# can.net
KiCad netlist of a schematic drawn in Altium Designer
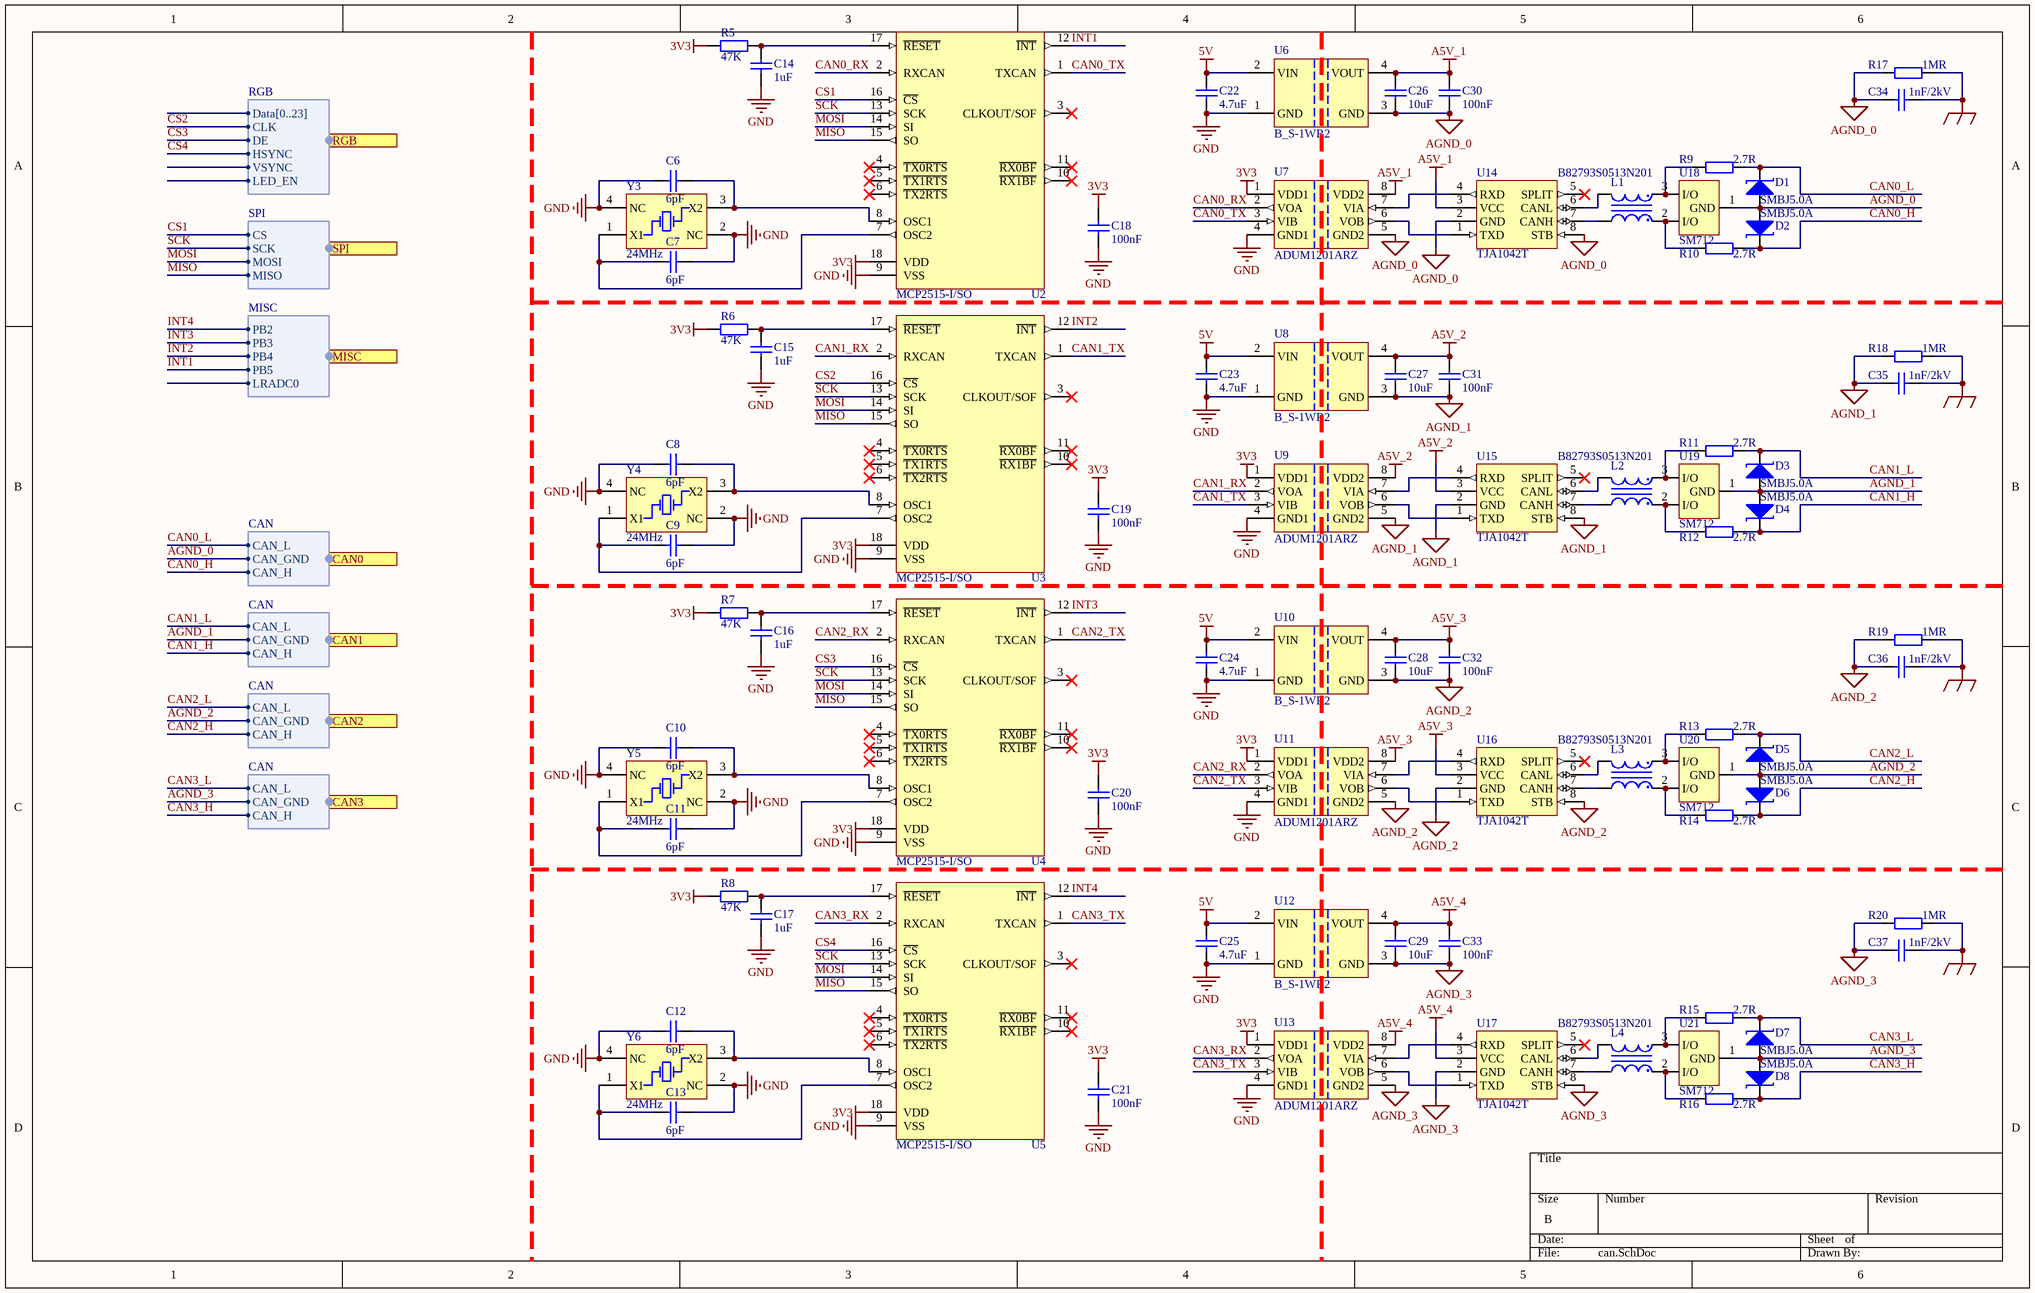
[diagram p0: can.SchDoc]

(export (version "E")
  (design (tool "Eeschema 10.0.6"))
  (components
    (comp (ref "C6")
      (value "6pF")
      (footprint "CAPC1608L")
      (description "Capacitor")
      (fields (field (name "PUBLISHER") "Altium Limited"))
      (libsource (lib "Peace的集成库") (part "Cap1"))
    )
    (comp (ref "C7")
      (value "6pF")
      (footprint "CAPC1608L")
      (description "Capacitor")
      (fields (field (name "PUBLISHER") "Altium Limited"))
      (libsource (lib "Peace的集成库") (part "Cap1"))
    )
    (comp (ref "C8")
      (value "6pF")
      (footprint "CAPC1608L")
      (description "Capacitor")
      (fields (field (name "PUBLISHER") "Altium Limited"))
      (libsource (lib "Peace的集成库") (part "Cap1"))
    )
    (comp (ref "C9")
      (value "6pF")
      (footprint "CAPC1608L")
      (description "Capacitor")
      (fields (field (name "PUBLISHER") "Altium Limited"))
      (libsource (lib "Peace的集成库") (part "Cap1"))
    )
    (comp (ref "C10")
      (value "6pF")
      (footprint "CAPC1608L")
      (description "Capacitor")
      (fields (field (name "PUBLISHER") "Altium Limited"))
      (libsource (lib "Peace的集成库") (part "Cap1"))
    )
    (comp (ref "C11")
      (value "6pF")
      (footprint "CAPC1608L")
      (description "Capacitor")
      (fields (field (name "PUBLISHER") "Altium Limited"))
      (libsource (lib "Peace的集成库") (part "Cap1"))
    )
    (comp (ref "C12")
      (value "6pF")
      (footprint "CAPC1608L")
      (description "Capacitor")
      (fields (field (name "PUBLISHER") "Altium Limited"))
      (libsource (lib "Peace的集成库") (part "Cap1"))
    )
    (comp (ref "C13")
      (value "6pF")
      (footprint "CAPC1608L")
      (description "Capacitor")
      (fields (field (name "PUBLISHER") "Altium Limited"))
      (libsource (lib "Peace的集成库") (part "Cap1"))
    )
    (comp (ref "C14")
      (value "1uF")
      (footprint "CAPC1608L")
      (description "Capacitor")
      (fields (field (name "PUBLISHER") "Altium Limited"))
      (libsource (lib "Peace的集成库") (part "Cap1"))
    )
    (comp (ref "C15")
      (value "1uF")
      (footprint "CAPC1608L")
      (description "Capacitor")
      (fields (field (name "PUBLISHER") "Altium Limited"))
      (libsource (lib "Peace的集成库") (part "Cap1"))
    )
    (comp (ref "C16")
      (value "1uF")
      (footprint "CAPC1608L")
      (description "Capacitor")
      (fields (field (name "PUBLISHER") "Altium Limited"))
      (libsource (lib "Peace的集成库") (part "Cap1"))
    )
    (comp (ref "C17")
      (value "1uF")
      (footprint "CAPC1608L")
      (description "Capacitor")
      (fields (field (name "PUBLISHER") "Altium Limited"))
      (libsource (lib "Peace的集成库") (part "Cap1"))
    )
    (comp (ref "C18")
      (value "100nF")
      (footprint "CAPC1608L")
      (description "Capacitor")
      (fields (field (name "PUBLISHER") "Altium Limited"))
      (libsource (lib "Peace的集成库") (part "Cap1"))
    )
    (comp (ref "C19")
      (value "100nF")
      (footprint "CAPC1608L")
      (description "Capacitor")
      (fields (field (name "PUBLISHER") "Altium Limited"))
      (libsource (lib "Peace的集成库") (part "Cap1"))
    )
    (comp (ref "C20")
      (value "100nF")
      (footprint "CAPC1608L")
      (description "Capacitor")
      (fields (field (name "PUBLISHER") "Altium Limited"))
      (libsource (lib "Peace的集成库") (part "Cap1"))
    )
    (comp (ref "C21")
      (value "100nF")
      (footprint "CAPC1608L")
      (description "Capacitor")
      (fields (field (name "PUBLISHER") "Altium Limited"))
      (libsource (lib "Peace的集成库") (part "Cap1"))
    )
    (comp (ref "C22")
      (value "4.7uF")
      (footprint "CAPC2012L")
      (description "Capacitor")
      (fields (field (name "PUBLISHER") "Altium Limited"))
      (libsource (lib "Peace的集成库") (part "Cap1"))
    )
    (comp (ref "C23")
      (value "4.7uF")
      (footprint "CAPC2012L")
      (description "Capacitor")
      (fields (field (name "PUBLISHER") "Altium Limited"))
      (libsource (lib "Peace的集成库") (part "Cap1"))
    )
    (comp (ref "C24")
      (value "4.7uF")
      (footprint "CAPC2012L")
      (description "Capacitor")
      (fields (field (name "PUBLISHER") "Altium Limited"))
      (libsource (lib "Peace的集成库") (part "Cap1"))
    )
    (comp (ref "C25")
      (value "4.7uF")
      (footprint "CAPC2012L")
      (description "Capacitor")
      (fields (field (name "PUBLISHER") "Altium Limited"))
      (libsource (lib "Peace的集成库") (part "Cap1"))
    )
    (comp (ref "C26")
      (value "10uF")
      (footprint "CAPC2012L")
      (description "Capacitor")
      (fields (field (name "PUBLISHER") "Altium Limited"))
      (libsource (lib "Peace的集成库") (part "Cap1"))
    )
    (comp (ref "C27")
      (value "10uF")
      (footprint "CAPC2012L")
      (description "Capacitor")
      (fields (field (name "PUBLISHER") "Altium Limited"))
      (libsource (lib "Peace的集成库") (part "Cap1"))
    )
    (comp (ref "C28")
      (value "10uF")
      (footprint "CAPC2012L")
      (description "Capacitor")
      (fields (field (name "PUBLISHER") "Altium Limited"))
      (libsource (lib "Peace的集成库") (part "Cap1"))
    )
    (comp (ref "C29")
      (value "10uF")
      (footprint "CAPC2012L")
      (description "Capacitor")
      (fields (field (name "PUBLISHER") "Altium Limited"))
      (libsource (lib "Peace的集成库") (part "Cap1"))
    )
    (comp (ref "C30")
      (value "100nF")
      (footprint "CAPC1608L")
      (description "Capacitor")
      (fields (field (name "PUBLISHER") "Altium Limited"))
      (libsource (lib "Peace的集成库") (part "Cap1"))
    )
    (comp (ref "C31")
      (value "100nF")
      (footprint "CAPC1608L")
      (description "Capacitor")
      (fields (field (name "PUBLISHER") "Altium Limited"))
      (libsource (lib "Peace的集成库") (part "Cap1"))
    )
    (comp (ref "C32")
      (value "100nF")
      (footprint "CAPC1608L")
      (description "Capacitor")
      (fields (field (name "PUBLISHER") "Altium Limited"))
      (libsource (lib "Peace的集成库") (part "Cap1"))
    )
    (comp (ref "C33")
      (value "100nF")
      (footprint "CAPC1608L")
      (description "Capacitor")
      (fields (field (name "PUBLISHER") "Altium Limited"))
      (libsource (lib "Peace的集成库") (part "Cap1"))
    )
    (comp (ref "C34")
      (value "1nF/2kV")
      (footprint "CAPC3216L")
      (description "Capacitor")
      (fields (field (name "PUBLISHER") "Altium Limited"))
      (libsource (lib "Peace的集成库") (part "Cap1"))
    )
    (comp (ref "C35")
      (value "1nF/2kV")
      (footprint "CAPC3216L")
      (description "Capacitor")
      (fields (field (name "PUBLISHER") "Altium Limited"))
      (libsource (lib "Peace的集成库") (part "Cap1"))
    )
    (comp (ref "C36")
      (value "1nF/2kV")
      (footprint "CAPC3216L")
      (description "Capacitor")
      (fields (field (name "PUBLISHER") "Altium Limited"))
      (libsource (lib "Peace的集成库") (part "Cap1"))
    )
    (comp (ref "C37")
      (value "1nF/2kV")
      (footprint "CAPC3216L")
      (description "Capacitor")
      (fields (field (name "PUBLISHER") "Altium Limited"))
      (libsource (lib "Peace的集成库") (part "Cap1"))
    )
    (comp (ref "D1")
      (value "SMBJ5.0A")
      (footprint "DO-214AA")
      (description "Transient Voltage Suppression (TVS) Diode")
      (fields (field (name "PUBLISHER") "Altium Limited"))
      (libsource (lib "Peace的集成库") (part "Tranzorb1"))
    )
    (comp (ref "D2")
      (value "SMBJ5.0A")
      (footprint "DO-214AA")
      (description "Transient Voltage Suppression (TVS) Diode")
      (fields (field (name "PUBLISHER") "Altium Limited"))
      (libsource (lib "Peace的集成库") (part "Tranzorb1"))
    )
    (comp (ref "D3")
      (value "SMBJ5.0A")
      (footprint "DO-214AA")
      (description "Transient Voltage Suppression (TVS) Diode")
      (fields (field (name "PUBLISHER") "Altium Limited"))
      (libsource (lib "Peace的集成库") (part "Tranzorb1"))
    )
    (comp (ref "D4")
      (value "SMBJ5.0A")
      (footprint "DO-214AA")
      (description "Transient Voltage Suppression (TVS) Diode")
      (fields (field (name "PUBLISHER") "Altium Limited"))
      (libsource (lib "Peace的集成库") (part "Tranzorb1"))
    )
    (comp (ref "D5")
      (value "SMBJ5.0A")
      (footprint "DO-214AA")
      (description "Transient Voltage Suppression (TVS) Diode")
      (fields (field (name "PUBLISHER") "Altium Limited"))
      (libsource (lib "Peace的集成库") (part "Tranzorb1"))
    )
    (comp (ref "D6")
      (value "SMBJ5.0A")
      (footprint "DO-214AA")
      (description "Transient Voltage Suppression (TVS) Diode")
      (fields (field (name "PUBLISHER") "Altium Limited"))
      (libsource (lib "Peace的集成库") (part "Tranzorb1"))
    )
    (comp (ref "D7")
      (value "SMBJ5.0A")
      (footprint "DO-214AA")
      (description "Transient Voltage Suppression (TVS) Diode")
      (fields (field (name "PUBLISHER") "Altium Limited"))
      (libsource (lib "Peace的集成库") (part "Tranzorb1"))
    )
    (comp (ref "D8")
      (value "SMBJ5.0A")
      (footprint "DO-214AA")
      (description "Transient Voltage Suppression (TVS) Diode")
      (fields (field (name "PUBLISHER") "Altium Limited"))
      (libsource (lib "Peace的集成库") (part "Tranzorb1"))
    )
    (comp (ref "L1")
      (value "B82793S0513N201")
      (footprint "IND0163-B")
      (description "共模电感")
      (fields (field (name "PUBLISHER") "Altium Limited"))
      (libsource (lib "Peace的集成库") (part "Inductor1"))
    )
    (comp (ref "L2")
      (value "B82793S0513N201")
      (footprint "IND0163-B")
      (description "共模电感")
      (fields (field (name "PUBLISHER") "Altium Limited"))
      (libsource (lib "Peace的集成库") (part "Inductor1"))
    )
    (comp (ref "L3")
      (value "B82793S0513N201")
      (footprint "IND0163-B")
      (description "共模电感")
      (fields (field (name "PUBLISHER") "Altium Limited"))
      (libsource (lib "Peace的集成库") (part "Inductor1"))
    )
    (comp (ref "L4")
      (value "B82793S0513N201")
      (footprint "IND0163-B")
      (description "共模电感")
      (fields (field (name "PUBLISHER") "Altium Limited"))
      (libsource (lib "Peace的集成库") (part "Inductor1"))
    )
    (comp (ref "R5")
      (value "47K")
      (footprint "RESC1608L")
      (description "Resistor")
      (fields (field (name "PUBLISHER") "Altium Limited"))
      (libsource (lib "") (part "Res1_1"))
    )
    (comp (ref "R6")
      (value "47K")
      (footprint "RESC1608L")
      (description "Resistor")
      (fields (field (name "PUBLISHER") "Altium Limited"))
      (libsource (lib "") (part "Res1_1"))
    )
    (comp (ref "R7")
      (value "47K")
      (footprint "RESC1608L")
      (description "Resistor")
      (fields (field (name "PUBLISHER") "Altium Limited"))
      (libsource (lib "") (part "Res1_1"))
    )
    (comp (ref "R8")
      (value "47K")
      (footprint "RESC1608L")
      (description "Resistor")
      (fields (field (name "PUBLISHER") "Altium Limited"))
      (libsource (lib "") (part "Res1_1"))
    )
    (comp (ref "R9")
      (value "2.7R")
      (footprint "RESC3216L")
      (description "Resistor")
      (fields (field (name "PUBLISHER") "Altium Limited"))
      (libsource (lib "Peace的集成库") (part "Res1"))
    )
    (comp (ref "R10")
      (value "2.7R")
      (footprint "RESC3216L")
      (description "Resistor")
      (fields (field (name "PUBLISHER") "Altium Limited"))
      (libsource (lib "Peace的集成库") (part "Res1"))
    )
    (comp (ref "R11")
      (value "2.7R")
      (footprint "RESC3216L")
      (description "Resistor")
      (fields (field (name "PUBLISHER") "Altium Limited"))
      (libsource (lib "Peace的集成库") (part "Res1"))
    )
    (comp (ref "R12")
      (value "2.7R")
      (footprint "RESC3216L")
      (description "Resistor")
      (fields (field (name "PUBLISHER") "Altium Limited"))
      (libsource (lib "Peace的集成库") (part "Res1"))
    )
    (comp (ref "R13")
      (value "2.7R")
      (footprint "RESC3216L")
      (description "Resistor")
      (fields (field (name "PUBLISHER") "Altium Limited"))
      (libsource (lib "Peace的集成库") (part "Res1"))
    )
    (comp (ref "R14")
      (value "2.7R")
      (footprint "RESC3216L")
      (description "Resistor")
      (fields (field (name "PUBLISHER") "Altium Limited"))
      (libsource (lib "Peace的集成库") (part "Res1"))
    )
    (comp (ref "R15")
      (value "2.7R")
      (footprint "RESC3216L")
      (description "Resistor")
      (fields (field (name "PUBLISHER") "Altium Limited"))
      (libsource (lib "Peace的集成库") (part "Res1"))
    )
    (comp (ref "R16")
      (value "2.7R")
      (footprint "RESC3216L")
      (description "Resistor")
      (fields (field (name "PUBLISHER") "Altium Limited"))
      (libsource (lib "Peace的集成库") (part "Res1"))
    )
    (comp (ref "R17")
      (value "1MR")
      (footprint "RESC3216L")
      (description "Resistor")
      (fields (field (name "PUBLISHER") "Altium Limited"))
      (libsource (lib "Peace的集成库") (part "Res1"))
    )
    (comp (ref "R18")
      (value "1MR")
      (footprint "RESC3216L")
      (description "Resistor")
      (fields (field (name "PUBLISHER") "Altium Limited"))
      (libsource (lib "Peace的集成库") (part "Res1"))
    )
    (comp (ref "R19")
      (value "1MR")
      (footprint "RESC3216L")
      (description "Resistor")
      (fields (field (name "PUBLISHER") "Altium Limited"))
      (libsource (lib "Peace的集成库") (part "Res1"))
    )
    (comp (ref "R20")
      (value "1MR")
      (footprint "RESC3216L")
      (description "Resistor")
      (fields (field (name "PUBLISHER") "Altium Limited"))
      (libsource (lib "Peace的集成库") (part "Res1"))
    )
    (comp (ref "U2")
      (value "MCP2515-I/SO")
      (footprint "SOIC18_N")
      (description "Stand-Alone CAN Controller With SPI Interface, 18-Pin SOIC, Industrial Temperature")
      (fields (field (name "PUBLISHER") "Altium Limited"))
      (libsource (lib "Peace的集成库") (part "MCP2515-I/SO"))
    )
    (comp (ref "U3")
      (value "MCP2515-I/SO")
      (footprint "SOIC18_N")
      (description "Stand-Alone CAN Controller With SPI Interface, 18-Pin SOIC, Industrial Temperature")
      (fields (field (name "PUBLISHER") "Altium Limited"))
      (libsource (lib "Peace的集成库") (part "MCP2515-I/SO"))
    )
    (comp (ref "U4")
      (value "MCP2515-I/SO")
      (footprint "SOIC18_N")
      (description "Stand-Alone CAN Controller With SPI Interface, 18-Pin SOIC, Industrial Temperature")
      (fields (field (name "PUBLISHER") "Altium Limited"))
      (libsource (lib "Peace的集成库") (part "MCP2515-I/SO"))
    )
    (comp (ref "U5")
      (value "MCP2515-I/SO")
      (footprint "SOIC18_N")
      (description "Stand-Alone CAN Controller With SPI Interface, 18-Pin SOIC, Industrial Temperature")
      (fields (field (name "PUBLISHER") "Altium Limited"))
      (libsource (lib "Peace的集成库") (part "MCP2515-I/SO"))
    )
    (comp (ref "U6")
      (value "B_S-1WR2")
      (footprint "B_S-1WR2")
      (description "DC/DC 模块电源 1W，定电压输入，隔离非稳压单路输出")
      (libsource (lib "原理图库") (part "B_S-1WR2"))
    )
    (comp (ref "U7")
      (value "ADUM1201ARZ")
      (footprint "SOIC8_L")
      (description "双通道数字隔离器（1/1通道方向性）")
      (libsource (lib "Peace的集成库") (part "ADUM1201"))
    )
    (comp (ref "U8")
      (value "B_S-1WR2")
      (footprint "B_S-1WR2")
      (description "DC/DC 模块电源 1W，定电压输入，隔离非稳压单路输出")
      (libsource (lib "原理图库") (part "B_S-1WR2"))
    )
    (comp (ref "U9")
      (value "ADUM1201ARZ")
      (footprint "SOIC8_L")
      (description "双通道数字隔离器（1/1通道方向性）")
      (libsource (lib "Peace的集成库") (part "ADUM1201"))
    )
    (comp (ref "U10")
      (value "B_S-1WR2")
      (footprint "B_S-1WR2")
      (description "DC/DC 模块电源 1W，定电压输入，隔离非稳压单路输出")
      (libsource (lib "原理图库") (part "B_S-1WR2"))
    )
    (comp (ref "U11")
      (value "ADUM1201ARZ")
      (footprint "SOIC8_L")
      (description "双通道数字隔离器（1/1通道方向性）")
      (libsource (lib "Peace的集成库") (part "ADUM1201"))
    )
    (comp (ref "U12")
      (value "B_S-1WR2")
      (footprint "B_S-1WR2")
      (description "DC/DC 模块电源 1W，定电压输入，隔离非稳压单路输出")
      (libsource (lib "原理图库") (part "B_S-1WR2"))
    )
    (comp (ref "U13")
      (value "ADUM1201ARZ")
      (footprint "SOIC8_L")
      (description "双通道数字隔离器（1/1通道方向性）")
      (libsource (lib "Peace的集成库") (part "ADUM1201"))
    )
    (comp (ref "U14")
      (value "TJA1042T")
      (footprint "SOIC8_L")
      (description "具有待机模式的高速CAN收发器")
      (libsource (lib "Peace的集成库") (part "TJA1042T"))
    )
    (comp (ref "U15")
      (value "TJA1042T")
      (footprint "SOIC8_L")
      (description "具有待机模式的高速CAN收发器")
      (libsource (lib "Peace的集成库") (part "TJA1042T"))
    )
    (comp (ref "U16")
      (value "TJA1042T")
      (footprint "SOIC8_L")
      (description "具有待机模式的高速CAN收发器")
      (libsource (lib "Peace的集成库") (part "TJA1042T"))
    )
    (comp (ref "U17")
      (value "TJA1042T")
      (footprint "SOIC8_L")
      (description "具有待机模式的高速CAN收发器")
      (libsource (lib "Peace的集成库") (part "TJA1042T"))
    )
    (comp (ref "U18") (value "SM712") (footprint "SOT23_L") (libsource (lib "Peace的集成库") (part "Tranzorb2")))
    (comp (ref "U19") (value "SM712") (footprint "SOT23_L") (libsource (lib "Peace的集成库") (part "Tranzorb2")))
    (comp (ref "U20") (value "SM712") (footprint "SOT23_L") (libsource (lib "Peace的集成库") (part "Tranzorb2")))
    (comp (ref "U21") (value "SM712") (footprint "SOT23_L") (libsource (lib "Peace的集成库") (part "Tranzorb2")))
    (comp (ref "Y3")
      (value "24MHz")
      (footprint "XTAL-3225")
      (description "Crystal Oscillator")
      (fields (field (name "PUBLISHER") "Altium Limited"))
      (libsource (lib "Peace的集成库") (part "XTAL_PASSIVE_4"))
    )
    (comp (ref "Y4")
      (value "24MHz")
      (footprint "XTAL-3225")
      (description "Crystal Oscillator")
      (fields (field (name "PUBLISHER") "Altium Limited"))
      (libsource (lib "Peace的集成库") (part "XTAL_PASSIVE_4"))
    )
    (comp (ref "Y5")
      (value "24MHz")
      (footprint "XTAL-3225")
      (description "Crystal Oscillator")
      (fields (field (name "PUBLISHER") "Altium Limited"))
      (libsource (lib "Peace的集成库") (part "XTAL_PASSIVE_4"))
    )
    (comp (ref "Y6")
      (value "24MHz")
      (footprint "XTAL-3225")
      (description "Crystal Oscillator")
      (fields (field (name "PUBLISHER") "Altium Limited"))
      (libsource (lib "Peace的集成库") (part "XTAL_PASSIVE_4"))
    )
  )
  (nets
    (net (code "6") (name "/CAN0_H") (class "Default")
      (node (ref "D2") (pin "2") (pinfunction "K_2") (pintype "passive"))
      (node (ref "R10") (pin "1") (pinfunction "1_1") (pintype "passive"))
    )
    (net (code "7") (name "/CAN0_L") (class "Default")
      (node (ref "D1") (pin "2") (pinfunction "K_2") (pintype "passive"))
      (node (ref "R9") (pin "1") (pinfunction "1_1") (pintype "passive"))
    )
    (net (code "8") (name "/CAN0_RX") (class "Default")
      (node (ref "U2") (pin "2") (pinfunction "RXCAN_2") (pintype "input"))
      (node (ref "U7") (pin "2") (pinfunction "VOA_2") (pintype "output"))
    )
    (net (code "9") (name "/CAN0_TX") (class "Default")
      (node (ref "U2") (pin "1") (pinfunction "TXCAN_1") (pintype "output"))
      (node (ref "U7") (pin "3") (pinfunction "VIB_3") (pintype "input"))
    )
    (net (code "10") (name "/CAN1_H") (class "Default")
      (node (ref "D4") (pin "2") (pinfunction "K_2") (pintype "passive"))
      (node (ref "R12") (pin "1") (pinfunction "1_1") (pintype "passive"))
    )
    (net (code "11") (name "/CAN1_L") (class "Default")
      (node (ref "D3") (pin "2") (pinfunction "K_2") (pintype "passive"))
      (node (ref "R11") (pin "1") (pinfunction "1_1") (pintype "passive"))
    )
    (net (code "12") (name "/CAN1_RX") (class "Default")
      (node (ref "U3") (pin "2") (pinfunction "RXCAN_2") (pintype "input"))
      (node (ref "U9") (pin "2") (pinfunction "VOA_2") (pintype "output"))
    )
    (net (code "13") (name "/CAN1_TX") (class "Default")
      (node (ref "U3") (pin "1") (pinfunction "TXCAN_1") (pintype "output"))
      (node (ref "U9") (pin "3") (pinfunction "VIB_3") (pintype "input"))
    )
    (net (code "14") (name "/CAN2_H") (class "Default")
      (node (ref "D6") (pin "2") (pinfunction "K_2") (pintype "passive"))
      (node (ref "R14") (pin "1") (pinfunction "1_1") (pintype "passive"))
    )
    (net (code "15") (name "/CAN2_L") (class "Default")
      (node (ref "D5") (pin "2") (pinfunction "K_2") (pintype "passive"))
      (node (ref "R13") (pin "1") (pinfunction "1_1") (pintype "passive"))
    )
    (net (code "16") (name "/CAN2_RX") (class "Default")
      (node (ref "U11") (pin "2") (pinfunction "VOA_2") (pintype "output"))
      (node (ref "U4") (pin "2") (pinfunction "RXCAN_2") (pintype "input"))
    )
    (net (code "17") (name "/CAN2_TX") (class "Default")
      (node (ref "U11") (pin "3") (pinfunction "VIB_3") (pintype "input"))
      (node (ref "U4") (pin "1") (pinfunction "TXCAN_1") (pintype "output"))
    )
    (net (code "18") (name "/CAN3_H") (class "Default")
      (node (ref "D8") (pin "2") (pinfunction "K_2") (pintype "passive"))
      (node (ref "R16") (pin "1") (pinfunction "1_1") (pintype "passive"))
    )
    (net (code "19") (name "/CAN3_L") (class "Default")
      (node (ref "D7") (pin "2") (pinfunction "K_2") (pintype "passive"))
      (node (ref "R15") (pin "1") (pinfunction "1_1") (pintype "passive"))
    )
    (net (code "20") (name "/CAN3_RX") (class "Default")
      (node (ref "U13") (pin "2") (pinfunction "VOA_2") (pintype "output"))
      (node (ref "U5") (pin "2") (pinfunction "RXCAN_2") (pintype "input"))
    )
    (net (code "21") (name "/CAN3_TX") (class "Default")
      (node (ref "U13") (pin "3") (pinfunction "VIB_3") (pintype "input"))
      (node (ref "U5") (pin "1") (pinfunction "TXCAN_1") (pintype "output"))
    )
    (net (code "22") (name "/CS1") (class "Default")
      (node (ref "U2") (pin "16") (pinfunction "~{CS}_16") (pintype "input"))
    )
    (net (code "23") (name "/CS2") (class "Default")
      (node (ref "U3") (pin "16") (pinfunction "~{CS}_16") (pintype "input"))
    )
    (net (code "24") (name "/CS3") (class "Default")
      (node (ref "U4") (pin "16") (pinfunction "~{CS}_16") (pintype "input"))
    )
    (net (code "25") (name "/CS4") (class "Default")
      (node (ref "U5") (pin "16") (pinfunction "~{CS}_16") (pintype "input"))
    )
    (net (code "26") (name "/INT1") (class "Default")
      (node (ref "U2") (pin "12") (pinfunction "~{INT}_12") (pintype "output"))
    )
    (net (code "27") (name "/INT2") (class "Default")
      (node (ref "U3") (pin "12") (pinfunction "~{INT}_12") (pintype "output"))
    )
    (net (code "28") (name "/INT3") (class "Default")
      (node (ref "U4") (pin "12") (pinfunction "~{INT}_12") (pintype "output"))
    )
    (net (code "29") (name "/INT4") (class "Default")
      (node (ref "U5") (pin "12") (pinfunction "~{INT}_12") (pintype "output"))
    )
    (net (code "30") (name "/MISO") (class "Default")
      (node (ref "U2") (pin "15") (pinfunction "SO_15") (pintype "output"))
      (node (ref "U3") (pin "15") (pinfunction "SO_15") (pintype "output"))
      (node (ref "U4") (pin "15") (pinfunction "SO_15") (pintype "output"))
      (node (ref "U5") (pin "15") (pinfunction "SO_15") (pintype "output"))
    )
    (net (code "31") (name "/MOSI") (class "Default")
      (node (ref "U2") (pin "14") (pinfunction "SI_14") (pintype "input"))
      (node (ref "U3") (pin "14") (pinfunction "SI_14") (pintype "input"))
      (node (ref "U4") (pin "14") (pinfunction "SI_14") (pintype "input"))
      (node (ref "U5") (pin "14") (pinfunction "SI_14") (pintype "input"))
    )
    (net (code "33") (name "/SCK") (class "Default")
      (node (ref "U2") (pin "13") (pinfunction "SCK_13") (pintype "input"))
      (node (ref "U3") (pin "13") (pinfunction "SCK_13") (pintype "input"))
      (node (ref "U4") (pin "13") (pinfunction "SCK_13") (pintype "input"))
      (node (ref "U5") (pin "13") (pinfunction "SCK_13") (pintype "input"))
    )
    (net (code "38") (name "3V3") (class "Default")
      (node (ref "C18") (pin "2") (pinfunction "2_2") (pintype "passive"))
      (node (ref "C19") (pin "2") (pinfunction "2_2") (pintype "passive"))
      (node (ref "C20") (pin "2") (pinfunction "2_2") (pintype "passive"))
      (node (ref "C21") (pin "2") (pinfunction "2_2") (pintype "passive"))
      (node (ref "R5") (pin "1") (pinfunction "1_1") (pintype "passive"))
      (node (ref "R6") (pin "1") (pinfunction "1_1") (pintype "passive"))
      (node (ref "R7") (pin "1") (pinfunction "1_1") (pintype "passive"))
      (node (ref "R8") (pin "1") (pinfunction "1_1") (pintype "passive"))
      (node (ref "U11") (pin "1") (pinfunction "VDD1_1") (pintype "power_in"))
      (node (ref "U13") (pin "1") (pinfunction "VDD1_1") (pintype "power_in"))
      (node (ref "U2") (pin "18") (pinfunction "VDD_18") (pintype "power_in"))
      (node (ref "U3") (pin "18") (pinfunction "VDD_18") (pintype "power_in"))
      (node (ref "U4") (pin "18") (pinfunction "VDD_18") (pintype "power_in"))
      (node (ref "U5") (pin "18") (pinfunction "VDD_18") (pintype "power_in"))
      (node (ref "U7") (pin "1") (pinfunction "VDD1_1") (pintype "power_in"))
      (node (ref "U9") (pin "1") (pinfunction "VDD1_1") (pintype "power_in"))
    )
    (net (code "39") (name "5V") (class "Default")
      (node (ref "C22") (pin "2") (pinfunction "2_2") (pintype "passive"))
      (node (ref "C23") (pin "2") (pinfunction "2_2") (pintype "passive"))
      (node (ref "C24") (pin "2") (pinfunction "2_2") (pintype "passive"))
      (node (ref "C25") (pin "2") (pinfunction "2_2") (pintype "passive"))
      (node (ref "U10") (pin "2") (pinfunction "VIN_2") (pintype "power_in"))
      (node (ref "U12") (pin "2") (pinfunction "VIN_2") (pintype "power_in"))
      (node (ref "U6") (pin "2") (pinfunction "VIN_2") (pintype "power_in"))
      (node (ref "U8") (pin "2") (pinfunction "VIN_2") (pintype "power_in"))
    )
    (net (code "40") (name "A5V_1") (class "Default")
      (node (ref "C26") (pin "2") (pinfunction "2_2") (pintype "passive"))
      (node (ref "C30") (pin "1") (pinfunction "1_1") (pintype "passive"))
      (node (ref "U14") (pin "3") (pinfunction "VCC_3") (pintype "power_in"))
      (node (ref "U6") (pin "4") (pinfunction "VOUT_4") (pintype "power_in"))
      (node (ref "U7") (pin "8") (pinfunction "VDD2_8") (pintype "power_in"))
    )
    (net (code "41") (name "A5V_2") (class "Default")
      (node (ref "C27") (pin "2") (pinfunction "2_2") (pintype "passive"))
      (node (ref "C31") (pin "1") (pinfunction "1_1") (pintype "passive"))
      (node (ref "U15") (pin "3") (pinfunction "VCC_3") (pintype "power_in"))
      (node (ref "U8") (pin "4") (pinfunction "VOUT_4") (pintype "power_in"))
      (node (ref "U9") (pin "8") (pinfunction "VDD2_8") (pintype "power_in"))
    )
    (net (code "42") (name "A5V_3") (class "Default")
      (node (ref "C28") (pin "2") (pinfunction "2_2") (pintype "passive"))
      (node (ref "C32") (pin "1") (pinfunction "1_1") (pintype "passive"))
      (node (ref "U10") (pin "4") (pinfunction "VOUT_4") (pintype "power_in"))
      (node (ref "U11") (pin "8") (pinfunction "VDD2_8") (pintype "power_in"))
      (node (ref "U16") (pin "3") (pinfunction "VCC_3") (pintype "power_in"))
    )
    (net (code "43") (name "A5V_4") (class "Default")
      (node (ref "C29") (pin "2") (pinfunction "2_2") (pintype "passive"))
      (node (ref "C33") (pin "1") (pinfunction "1_1") (pintype "passive"))
      (node (ref "U12") (pin "4") (pinfunction "VOUT_4") (pintype "power_in"))
      (node (ref "U13") (pin "8") (pinfunction "VDD2_8") (pintype "power_in"))
      (node (ref "U17") (pin "3") (pinfunction "VCC_3") (pintype "power_in"))
    )
    (net (code "44") (name "AGND_0") (class "Default")
      (node (ref "C26") (pin "1") (pinfunction "1_1") (pintype "passive"))
      (node (ref "C30") (pin "2") (pinfunction "2_2") (pintype "passive"))
      (node (ref "C34") (pin "1") (pinfunction "1_1") (pintype "passive"))
      (node (ref "D1") (pin "1") (pinfunction "A_1") (pintype "passive"))
      (node (ref "D2") (pin "1") (pinfunction "A_1") (pintype "passive"))
      (node (ref "R17") (pin "2") (pinfunction "2_2") (pintype "passive"))
      (node (ref "U14") (pin "2") (pinfunction "GND_2") (pintype "power_in"))
      (node (ref "U14") (pin "8") (pinfunction "STB_8") (pintype "input"))
      (node (ref "U18") (pin "1") (pinfunction "GND_1") (pintype "power_in"))
      (node (ref "U6") (pin "3") (pinfunction "GND_3") (pintype "power_in"))
      (node (ref "U7") (pin "5") (pinfunction "GND2_5") (pintype "power_in"))
    )
    (net (code "45") (name "AGND_1") (class "Default")
      (node (ref "C27") (pin "1") (pinfunction "1_1") (pintype "passive"))
      (node (ref "C31") (pin "2") (pinfunction "2_2") (pintype "passive"))
      (node (ref "C35") (pin "1") (pinfunction "1_1") (pintype "passive"))
      (node (ref "D3") (pin "1") (pinfunction "A_1") (pintype "passive"))
      (node (ref "D4") (pin "1") (pinfunction "A_1") (pintype "passive"))
      (node (ref "R18") (pin "2") (pinfunction "2_2") (pintype "passive"))
      (node (ref "U15") (pin "2") (pinfunction "GND_2") (pintype "power_in"))
      (node (ref "U15") (pin "8") (pinfunction "STB_8") (pintype "input"))
      (node (ref "U19") (pin "1") (pinfunction "GND_1") (pintype "power_in"))
      (node (ref "U8") (pin "3") (pinfunction "GND_3") (pintype "power_in"))
      (node (ref "U9") (pin "5") (pinfunction "GND2_5") (pintype "power_in"))
    )
    (net (code "46") (name "AGND_2") (class "Default")
      (node (ref "C28") (pin "1") (pinfunction "1_1") (pintype "passive"))
      (node (ref "C32") (pin "2") (pinfunction "2_2") (pintype "passive"))
      (node (ref "C36") (pin "1") (pinfunction "1_1") (pintype "passive"))
      (node (ref "D5") (pin "1") (pinfunction "A_1") (pintype "passive"))
      (node (ref "D6") (pin "1") (pinfunction "A_1") (pintype "passive"))
      (node (ref "R19") (pin "2") (pinfunction "2_2") (pintype "passive"))
      (node (ref "U10") (pin "3") (pinfunction "GND_3") (pintype "power_in"))
      (node (ref "U11") (pin "5") (pinfunction "GND2_5") (pintype "power_in"))
      (node (ref "U16") (pin "2") (pinfunction "GND_2") (pintype "power_in"))
      (node (ref "U16") (pin "8") (pinfunction "STB_8") (pintype "input"))
      (node (ref "U20") (pin "1") (pinfunction "GND_1") (pintype "power_in"))
    )
    (net (code "47") (name "AGND_3") (class "Default")
      (node (ref "C29") (pin "1") (pinfunction "1_1") (pintype "passive"))
      (node (ref "C33") (pin "2") (pinfunction "2_2") (pintype "passive"))
      (node (ref "C37") (pin "1") (pinfunction "1_1") (pintype "passive"))
      (node (ref "D7") (pin "1") (pinfunction "A_1") (pintype "passive"))
      (node (ref "D8") (pin "1") (pinfunction "A_1") (pintype "passive"))
      (node (ref "R20") (pin "2") (pinfunction "2_2") (pintype "passive"))
      (node (ref "U12") (pin "3") (pinfunction "GND_3") (pintype "power_in"))
      (node (ref "U13") (pin "5") (pinfunction "GND2_5") (pintype "power_in"))
      (node (ref "U17") (pin "2") (pinfunction "GND_2") (pintype "power_in"))
      (node (ref "U17") (pin "8") (pinfunction "STB_8") (pintype "input"))
      (node (ref "U21") (pin "1") (pinfunction "GND_1") (pintype "power_in"))
    )
    (net (code "48") (name "EARTH") (class "Default")
      (node (ref "C34") (pin "2") (pinfunction "2_2") (pintype "passive"))
      (node (ref "C35") (pin "2") (pinfunction "2_2") (pintype "passive"))
      (node (ref "C36") (pin "2") (pinfunction "2_2") (pintype "passive"))
      (node (ref "C37") (pin "2") (pinfunction "2_2") (pintype "passive"))
      (node (ref "R17") (pin "1") (pinfunction "1_1") (pintype "passive"))
      (node (ref "R18") (pin "1") (pinfunction "1_1") (pintype "passive"))
      (node (ref "R19") (pin "1") (pinfunction "1_1") (pintype "passive"))
      (node (ref "R20") (pin "1") (pinfunction "1_1") (pintype "passive"))
    )
    (net (code "49") (name "GND") (class "Default")
      (node (ref "C10") (pin "1") (pinfunction "1_1") (pintype "passive"))
      (node (ref "C11") (pin "2") (pinfunction "2_2") (pintype "passive"))
      (node (ref "C12") (pin "1") (pinfunction "1_1") (pintype "passive"))
      (node (ref "C13") (pin "2") (pinfunction "2_2") (pintype "passive"))
      (node (ref "C14") (pin "1") (pinfunction "1_1") (pintype "passive"))
      (node (ref "C15") (pin "1") (pinfunction "1_1") (pintype "passive"))
      (node (ref "C16") (pin "1") (pinfunction "1_1") (pintype "passive"))
      (node (ref "C17") (pin "1") (pinfunction "1_1") (pintype "passive"))
      (node (ref "C18") (pin "1") (pinfunction "1_1") (pintype "passive"))
      (node (ref "C19") (pin "1") (pinfunction "1_1") (pintype "passive"))
      (node (ref "C20") (pin "1") (pinfunction "1_1") (pintype "passive"))
      (node (ref "C21") (pin "1") (pinfunction "1_1") (pintype "passive"))
      (node (ref "C22") (pin "1") (pinfunction "1_1") (pintype "passive"))
      (node (ref "C23") (pin "1") (pinfunction "1_1") (pintype "passive"))
      (node (ref "C24") (pin "1") (pinfunction "1_1") (pintype "passive"))
      (node (ref "C25") (pin "1") (pinfunction "1_1") (pintype "passive"))
      (node (ref "C6") (pin "1") (pinfunction "1_1") (pintype "passive"))
      (node (ref "C7") (pin "2") (pinfunction "2_2") (pintype "passive"))
      (node (ref "C8") (pin "1") (pinfunction "1_1") (pintype "passive"))
      (node (ref "C9") (pin "2") (pinfunction "2_2") (pintype "passive"))
      (node (ref "U10") (pin "1") (pinfunction "GND_1") (pintype "power_in"))
      (node (ref "U11") (pin "4") (pinfunction "GND1_4") (pintype "power_in"))
      (node (ref "U12") (pin "1") (pinfunction "GND_1") (pintype "power_in"))
      (node (ref "U13") (pin "4") (pinfunction "GND1_4") (pintype "power_in"))
      (node (ref "U2") (pin "9") (pinfunction "VSS_9") (pintype "power_in"))
      (node (ref "U3") (pin "9") (pinfunction "VSS_9") (pintype "power_in"))
      (node (ref "U4") (pin "9") (pinfunction "VSS_9") (pintype "power_in"))
      (node (ref "U5") (pin "9") (pinfunction "VSS_9") (pintype "power_in"))
      (node (ref "U6") (pin "1") (pinfunction "GND_1") (pintype "power_in"))
      (node (ref "U7") (pin "4") (pinfunction "GND1_4") (pintype "power_in"))
      (node (ref "U8") (pin "1") (pinfunction "GND_1") (pintype "power_in"))
      (node (ref "U9") (pin "4") (pinfunction "GND1_4") (pintype "power_in"))
      (node (ref "Y3") (pin "2") (pinfunction "NC_2") (pintype "passive"))
      (node (ref "Y3") (pin "4") (pinfunction "NC_4") (pintype "passive"))
      (node (ref "Y4") (pin "2") (pinfunction "NC_2") (pintype "passive"))
      (node (ref "Y4") (pin "4") (pinfunction "NC_4") (pintype "passive"))
      (node (ref "Y5") (pin "2") (pinfunction "NC_2") (pintype "passive"))
      (node (ref "Y5") (pin "4") (pinfunction "NC_4") (pintype "passive"))
      (node (ref "Y6") (pin "2") (pinfunction "NC_2") (pintype "passive"))
      (node (ref "Y6") (pin "4") (pinfunction "NC_4") (pintype "passive"))
    )
    (net (code "50") (name "Net-(L1-Pad1)") (class "Default")
      (node (ref "L1") (pin "1") (pinfunction "1_1") (pintype "passive"))
      (node (ref "R10") (pin "2") (pinfunction "2_2") (pintype "passive"))
      (node (ref "U18") (pin "2") (pinfunction "I/O_2") (pintype "power_in"))
    )
    (net (code "51") (name "Net-(L1-Pad4)") (class "Default")
      (node (ref "L1") (pin "4") (pinfunction "4_4") (pintype "passive"))
      (node (ref "R9") (pin "2") (pinfunction "2_2") (pintype "passive"))
      (node (ref "U18") (pin "3") (pinfunction "I/O_3") (pintype "power_in"))
    )
    (net (code "52") (name "Net-(L2-Pad1)") (class "Default")
      (node (ref "L2") (pin "1") (pinfunction "1_1") (pintype "passive"))
      (node (ref "R12") (pin "2") (pinfunction "2_2") (pintype "passive"))
      (node (ref "U19") (pin "2") (pinfunction "I/O_2") (pintype "power_in"))
    )
    (net (code "53") (name "Net-(L2-Pad4)") (class "Default")
      (node (ref "L2") (pin "4") (pinfunction "4_4") (pintype "passive"))
      (node (ref "R11") (pin "2") (pinfunction "2_2") (pintype "passive"))
      (node (ref "U19") (pin "3") (pinfunction "I/O_3") (pintype "power_in"))
    )
    (net (code "54") (name "Net-(L3-Pad1)") (class "Default")
      (node (ref "L3") (pin "1") (pinfunction "1_1") (pintype "passive"))
      (node (ref "R14") (pin "2") (pinfunction "2_2") (pintype "passive"))
      (node (ref "U20") (pin "2") (pinfunction "I/O_2") (pintype "power_in"))
    )
    (net (code "55") (name "Net-(L3-Pad4)") (class "Default")
      (node (ref "L3") (pin "4") (pinfunction "4_4") (pintype "passive"))
      (node (ref "R13") (pin "2") (pinfunction "2_2") (pintype "passive"))
      (node (ref "U20") (pin "3") (pinfunction "I/O_3") (pintype "power_in"))
    )
    (net (code "56") (name "Net-(L4-Pad1)") (class "Default")
      (node (ref "L4") (pin "1") (pinfunction "1_1") (pintype "passive"))
      (node (ref "R16") (pin "2") (pinfunction "2_2") (pintype "passive"))
      (node (ref "U21") (pin "2") (pinfunction "I/O_2") (pintype "power_in"))
    )
    (net (code "57") (name "Net-(L4-Pad4)") (class "Default")
      (node (ref "L4") (pin "4") (pinfunction "4_4") (pintype "passive"))
      (node (ref "R15") (pin "2") (pinfunction "2_2") (pintype "passive"))
      (node (ref "U21") (pin "3") (pinfunction "I/O_3") (pintype "power_in"))
    )
    (net (code "58") (name "Net-(U2-OSC1)") (class "Default")
      (node (ref "C6") (pin "2") (pinfunction "2_2") (pintype "passive"))
      (node (ref "U2") (pin "8") (pinfunction "OSC1_8") (pintype "input"))
      (node (ref "Y3") (pin "3") (pinfunction "X2_3") (pintype "passive"))
    )
    (net (code "59") (name "Net-(U2-OSC2)") (class "Default")
      (node (ref "C7") (pin "1") (pinfunction "1_1") (pintype "passive"))
      (node (ref "U2") (pin "7") (pinfunction "OSC2_7") (pintype "output"))
      (node (ref "Y3") (pin "1") (pinfunction "X1_1") (pintype "passive"))
    )
    (net (code "60") (name "Net-(U2-~{RESET})") (class "Default")
      (node (ref "C14") (pin "2") (pinfunction "2_2") (pintype "passive"))
      (node (ref "R5") (pin "2") (pinfunction "2_2") (pintype "passive"))
      (node (ref "U2") (pin "17") (pinfunction "~{RESET}_17") (pintype "input"))
    )
    (net (code "61") (name "Net-(U3-OSC1)") (class "Default")
      (node (ref "C8") (pin "2") (pinfunction "2_2") (pintype "passive"))
      (node (ref "U3") (pin "8") (pinfunction "OSC1_8") (pintype "input"))
      (node (ref "Y4") (pin "3") (pinfunction "X2_3") (pintype "passive"))
    )
    (net (code "62") (name "Net-(U3-OSC2)") (class "Default")
      (node (ref "C9") (pin "1") (pinfunction "1_1") (pintype "passive"))
      (node (ref "U3") (pin "7") (pinfunction "OSC2_7") (pintype "output"))
      (node (ref "Y4") (pin "1") (pinfunction "X1_1") (pintype "passive"))
    )
    (net (code "63") (name "Net-(U3-~{RESET})") (class "Default")
      (node (ref "C15") (pin "2") (pinfunction "2_2") (pintype "passive"))
      (node (ref "R6") (pin "2") (pinfunction "2_2") (pintype "passive"))
      (node (ref "U3") (pin "17") (pinfunction "~{RESET}_17") (pintype "input"))
    )
    (net (code "64") (name "Net-(U4-OSC1)") (class "Default")
      (node (ref "C10") (pin "2") (pinfunction "2_2") (pintype "passive"))
      (node (ref "U4") (pin "8") (pinfunction "OSC1_8") (pintype "input"))
      (node (ref "Y5") (pin "3") (pinfunction "X2_3") (pintype "passive"))
    )
    (net (code "65") (name "Net-(U4-OSC2)") (class "Default")
      (node (ref "C11") (pin "1") (pinfunction "1_1") (pintype "passive"))
      (node (ref "U4") (pin "7") (pinfunction "OSC2_7") (pintype "output"))
      (node (ref "Y5") (pin "1") (pinfunction "X1_1") (pintype "passive"))
    )
    (net (code "66") (name "Net-(U4-~{RESET})") (class "Default")
      (node (ref "C16") (pin "2") (pinfunction "2_2") (pintype "passive"))
      (node (ref "R7") (pin "2") (pinfunction "2_2") (pintype "passive"))
      (node (ref "U4") (pin "17") (pinfunction "~{RESET}_17") (pintype "input"))
    )
    (net (code "67") (name "Net-(U5-OSC1)") (class "Default")
      (node (ref "C12") (pin "2") (pinfunction "2_2") (pintype "passive"))
      (node (ref "U5") (pin "8") (pinfunction "OSC1_8") (pintype "input"))
      (node (ref "Y6") (pin "3") (pinfunction "X2_3") (pintype "passive"))
    )
    (net (code "68") (name "Net-(U5-OSC2)") (class "Default")
      (node (ref "C13") (pin "1") (pinfunction "1_1") (pintype "passive"))
      (node (ref "U5") (pin "7") (pinfunction "OSC2_7") (pintype "output"))
      (node (ref "Y6") (pin "1") (pinfunction "X1_1") (pintype "passive"))
    )
    (net (code "69") (name "Net-(U5-~{RESET})") (class "Default")
      (node (ref "C17") (pin "2") (pinfunction "2_2") (pintype "passive"))
      (node (ref "R8") (pin "2") (pinfunction "2_2") (pintype "passive"))
      (node (ref "U5") (pin "17") (pinfunction "~{RESET}_17") (pintype "input"))
    )
    (net (code "70") (name "Net-(U11-VIA)") (class "Default")
      (node (ref "U11") (pin "7") (pinfunction "VIA_7") (pintype "input"))
      (node (ref "U16") (pin "4") (pinfunction "RXD_4") (pintype "output"))
    )
    (net (code "71") (name "Net-(U11-VOB)") (class "Default")
      (node (ref "U11") (pin "6") (pinfunction "VOB_6") (pintype "output"))
      (node (ref "U16") (pin "1") (pinfunction "TXD_1") (pintype "input"))
    )
    (net (code "72") (name "Net-(U13-VIA)") (class "Default")
      (node (ref "U13") (pin "7") (pinfunction "VIA_7") (pintype "input"))
      (node (ref "U17") (pin "4") (pinfunction "RXD_4") (pintype "output"))
    )
    (net (code "73") (name "Net-(U13-VOB)") (class "Default")
      (node (ref "U13") (pin "6") (pinfunction "VOB_6") (pintype "output"))
      (node (ref "U17") (pin "1") (pinfunction "TXD_1") (pintype "input"))
    )
    (net (code "74") (name "Net-(U14-CANH)") (class "Default")
      (node (ref "L1") (pin "2") (pinfunction "2_2") (pintype "passive"))
      (node (ref "U14") (pin "7") (pinfunction "CANH_7") (pintype "bidirectional"))
    )
    (net (code "75") (name "Net-(U14-CANL)") (class "Default")
      (node (ref "L1") (pin "3") (pinfunction "3_3") (pintype "passive"))
      (node (ref "U14") (pin "6") (pinfunction "CANL_6") (pintype "bidirectional"))
    )
    (net (code "76") (name "Net-(U14-RXD)") (class "Default")
      (node (ref "U14") (pin "4") (pinfunction "RXD_4") (pintype "output"))
      (node (ref "U7") (pin "7") (pinfunction "VIA_7") (pintype "input"))
    )
    (net (code "77") (name "Net-(U14-TXD)") (class "Default")
      (node (ref "U14") (pin "1") (pinfunction "TXD_1") (pintype "input"))
      (node (ref "U7") (pin "6") (pinfunction "VOB_6") (pintype "output"))
    )
    (net (code "78") (name "Net-(U15-CANH)") (class "Default")
      (node (ref "L2") (pin "2") (pinfunction "2_2") (pintype "passive"))
      (node (ref "U15") (pin "7") (pinfunction "CANH_7") (pintype "bidirectional"))
    )
    (net (code "79") (name "Net-(U15-CANL)") (class "Default")
      (node (ref "L2") (pin "3") (pinfunction "3_3") (pintype "passive"))
      (node (ref "U15") (pin "6") (pinfunction "CANL_6") (pintype "bidirectional"))
    )
    (net (code "80") (name "Net-(U15-RXD)") (class "Default")
      (node (ref "U15") (pin "4") (pinfunction "RXD_4") (pintype "output"))
      (node (ref "U9") (pin "7") (pinfunction "VIA_7") (pintype "input"))
    )
    (net (code "81") (name "Net-(U15-TXD)") (class "Default")
      (node (ref "U15") (pin "1") (pinfunction "TXD_1") (pintype "input"))
      (node (ref "U9") (pin "6") (pinfunction "VOB_6") (pintype "output"))
    )
    (net (code "82") (name "Net-(U16-CANH)") (class "Default")
      (node (ref "L3") (pin "2") (pinfunction "2_2") (pintype "passive"))
      (node (ref "U16") (pin "7") (pinfunction "CANH_7") (pintype "bidirectional"))
    )
    (net (code "83") (name "Net-(U16-CANL)") (class "Default")
      (node (ref "L3") (pin "3") (pinfunction "3_3") (pintype "passive"))
      (node (ref "U16") (pin "6") (pinfunction "CANL_6") (pintype "bidirectional"))
    )
    (net (code "84") (name "Net-(U17-CANH)") (class "Default")
      (node (ref "L4") (pin "2") (pinfunction "2_2") (pintype "passive"))
      (node (ref "U17") (pin "7") (pinfunction "CANH_7") (pintype "bidirectional"))
    )
    (net (code "85") (name "Net-(U17-CANL)") (class "Default")
      (node (ref "L4") (pin "3") (pinfunction "3_3") (pintype "passive"))
      (node (ref "U17") (pin "6") (pinfunction "CANL_6") (pintype "bidirectional"))
    )
    (net (code "86") (name "unconnected-(U2-CLKOUT{slash}SOF-Pad3)") (class "Default")
      (node (ref "U2") (pin "3") (pinfunction "CLKOUT/SOF_3") (pintype "output+no_connect"))
    )
    (net (code "87") (name "unconnected-(U2-~{RX0BF}-Pad11)") (class "Default")
      (node (ref "U2") (pin "11") (pinfunction "~{RX0BF}_11") (pintype "output+no_connect"))
    )
    (net (code "88") (name "unconnected-(U2-~{RX1BF}-Pad10)") (class "Default")
      (node (ref "U2") (pin "10") (pinfunction "~{RX1BF}_10") (pintype "output+no_connect"))
    )
    (net (code "89") (name "unconnected-(U2-~{TX0RTS}-Pad4)") (class "Default")
      (node (ref "U2") (pin "4") (pinfunction "~{TX0RTS}_4") (pintype "input+no_connect"))
    )
    (net (code "90") (name "unconnected-(U2-~{TX1RTS}-Pad5)") (class "Default")
      (node (ref "U2") (pin "5") (pinfunction "~{TX1RTS}_5") (pintype "input+no_connect"))
    )
    (net (code "91") (name "unconnected-(U2-~{TX2RTS}-Pad6)") (class "Default")
      (node (ref "U2") (pin "6") (pinfunction "~{TX2RTS}_6") (pintype "input+no_connect"))
    )
    (net (code "92") (name "unconnected-(U3-CLKOUT{slash}SOF-Pad3)") (class "Default")
      (node (ref "U3") (pin "3") (pinfunction "CLKOUT/SOF_3") (pintype "output+no_connect"))
    )
    (net (code "93") (name "unconnected-(U3-~{RX0BF}-Pad11)") (class "Default")
      (node (ref "U3") (pin "11") (pinfunction "~{RX0BF}_11") (pintype "output+no_connect"))
    )
    (net (code "94") (name "unconnected-(U3-~{RX1BF}-Pad10)") (class "Default")
      (node (ref "U3") (pin "10") (pinfunction "~{RX1BF}_10") (pintype "output+no_connect"))
    )
    (net (code "95") (name "unconnected-(U3-~{TX0RTS}-Pad4)") (class "Default")
      (node (ref "U3") (pin "4") (pinfunction "~{TX0RTS}_4") (pintype "input+no_connect"))
    )
    (net (code "96") (name "unconnected-(U3-~{TX1RTS}-Pad5)") (class "Default")
      (node (ref "U3") (pin "5") (pinfunction "~{TX1RTS}_5") (pintype "input+no_connect"))
    )
    (net (code "97") (name "unconnected-(U3-~{TX2RTS}-Pad6)") (class "Default")
      (node (ref "U3") (pin "6") (pinfunction "~{TX2RTS}_6") (pintype "input+no_connect"))
    )
    (net (code "98") (name "unconnected-(U4-CLKOUT{slash}SOF-Pad3)") (class "Default")
      (node (ref "U4") (pin "3") (pinfunction "CLKOUT/SOF_3") (pintype "output+no_connect"))
    )
    (net (code "99") (name "unconnected-(U4-~{RX0BF}-Pad11)") (class "Default")
      (node (ref "U4") (pin "11") (pinfunction "~{RX0BF}_11") (pintype "output+no_connect"))
    )
    (net (code "100") (name "unconnected-(U4-~{RX1BF}-Pad10)") (class "Default")
      (node (ref "U4") (pin "10") (pinfunction "~{RX1BF}_10") (pintype "output+no_connect"))
    )
    (net (code "101") (name "unconnected-(U4-~{TX0RTS}-Pad4)") (class "Default")
      (node (ref "U4") (pin "4") (pinfunction "~{TX0RTS}_4") (pintype "input+no_connect"))
    )
    (net (code "102") (name "unconnected-(U4-~{TX1RTS}-Pad5)") (class "Default")
      (node (ref "U4") (pin "5") (pinfunction "~{TX1RTS}_5") (pintype "input+no_connect"))
    )
    (net (code "103") (name "unconnected-(U4-~{TX2RTS}-Pad6)") (class "Default")
      (node (ref "U4") (pin "6") (pinfunction "~{TX2RTS}_6") (pintype "input+no_connect"))
    )
    (net (code "104") (name "unconnected-(U5-CLKOUT{slash}SOF-Pad3)") (class "Default")
      (node (ref "U5") (pin "3") (pinfunction "CLKOUT/SOF_3") (pintype "output+no_connect"))
    )
    (net (code "105") (name "unconnected-(U5-~{RX0BF}-Pad11)") (class "Default")
      (node (ref "U5") (pin "11") (pinfunction "~{RX0BF}_11") (pintype "output+no_connect"))
    )
    (net (code "106") (name "unconnected-(U5-~{RX1BF}-Pad10)") (class "Default")
      (node (ref "U5") (pin "10") (pinfunction "~{RX1BF}_10") (pintype "output+no_connect"))
    )
    (net (code "107") (name "unconnected-(U5-~{TX0RTS}-Pad4)") (class "Default")
      (node (ref "U5") (pin "4") (pinfunction "~{TX0RTS}_4") (pintype "input+no_connect"))
    )
    (net (code "108") (name "unconnected-(U5-~{TX1RTS}-Pad5)") (class "Default")
      (node (ref "U5") (pin "5") (pinfunction "~{TX1RTS}_5") (pintype "input+no_connect"))
    )
    (net (code "109") (name "unconnected-(U5-~{TX2RTS}-Pad6)") (class "Default")
      (node (ref "U5") (pin "6") (pinfunction "~{TX2RTS}_6") (pintype "input+no_connect"))
    )
    (net (code "110") (name "unconnected-(U14-SPLIT-Pad5)") (class "Default")
      (node (ref "U14") (pin "5") (pinfunction "SPLIT_5") (pintype "output+no_connect"))
    )
    (net (code "111") (name "unconnected-(U15-SPLIT-Pad5)") (class "Default")
      (node (ref "U15") (pin "5") (pinfunction "SPLIT_5") (pintype "output+no_connect"))
    )
    (net (code "112") (name "unconnected-(U16-SPLIT-Pad5)") (class "Default")
      (node (ref "U16") (pin "5") (pinfunction "SPLIT_5") (pintype "output+no_connect"))
    )
    (net (code "113") (name "unconnected-(U17-SPLIT-Pad5)") (class "Default")
      (node (ref "U17") (pin "5") (pinfunction "SPLIT_5") (pintype "output+no_connect"))
    )
  )
)
